# Attenuaverting_VCA.net
KiCad netlist of a schematic drawn in EAGLE
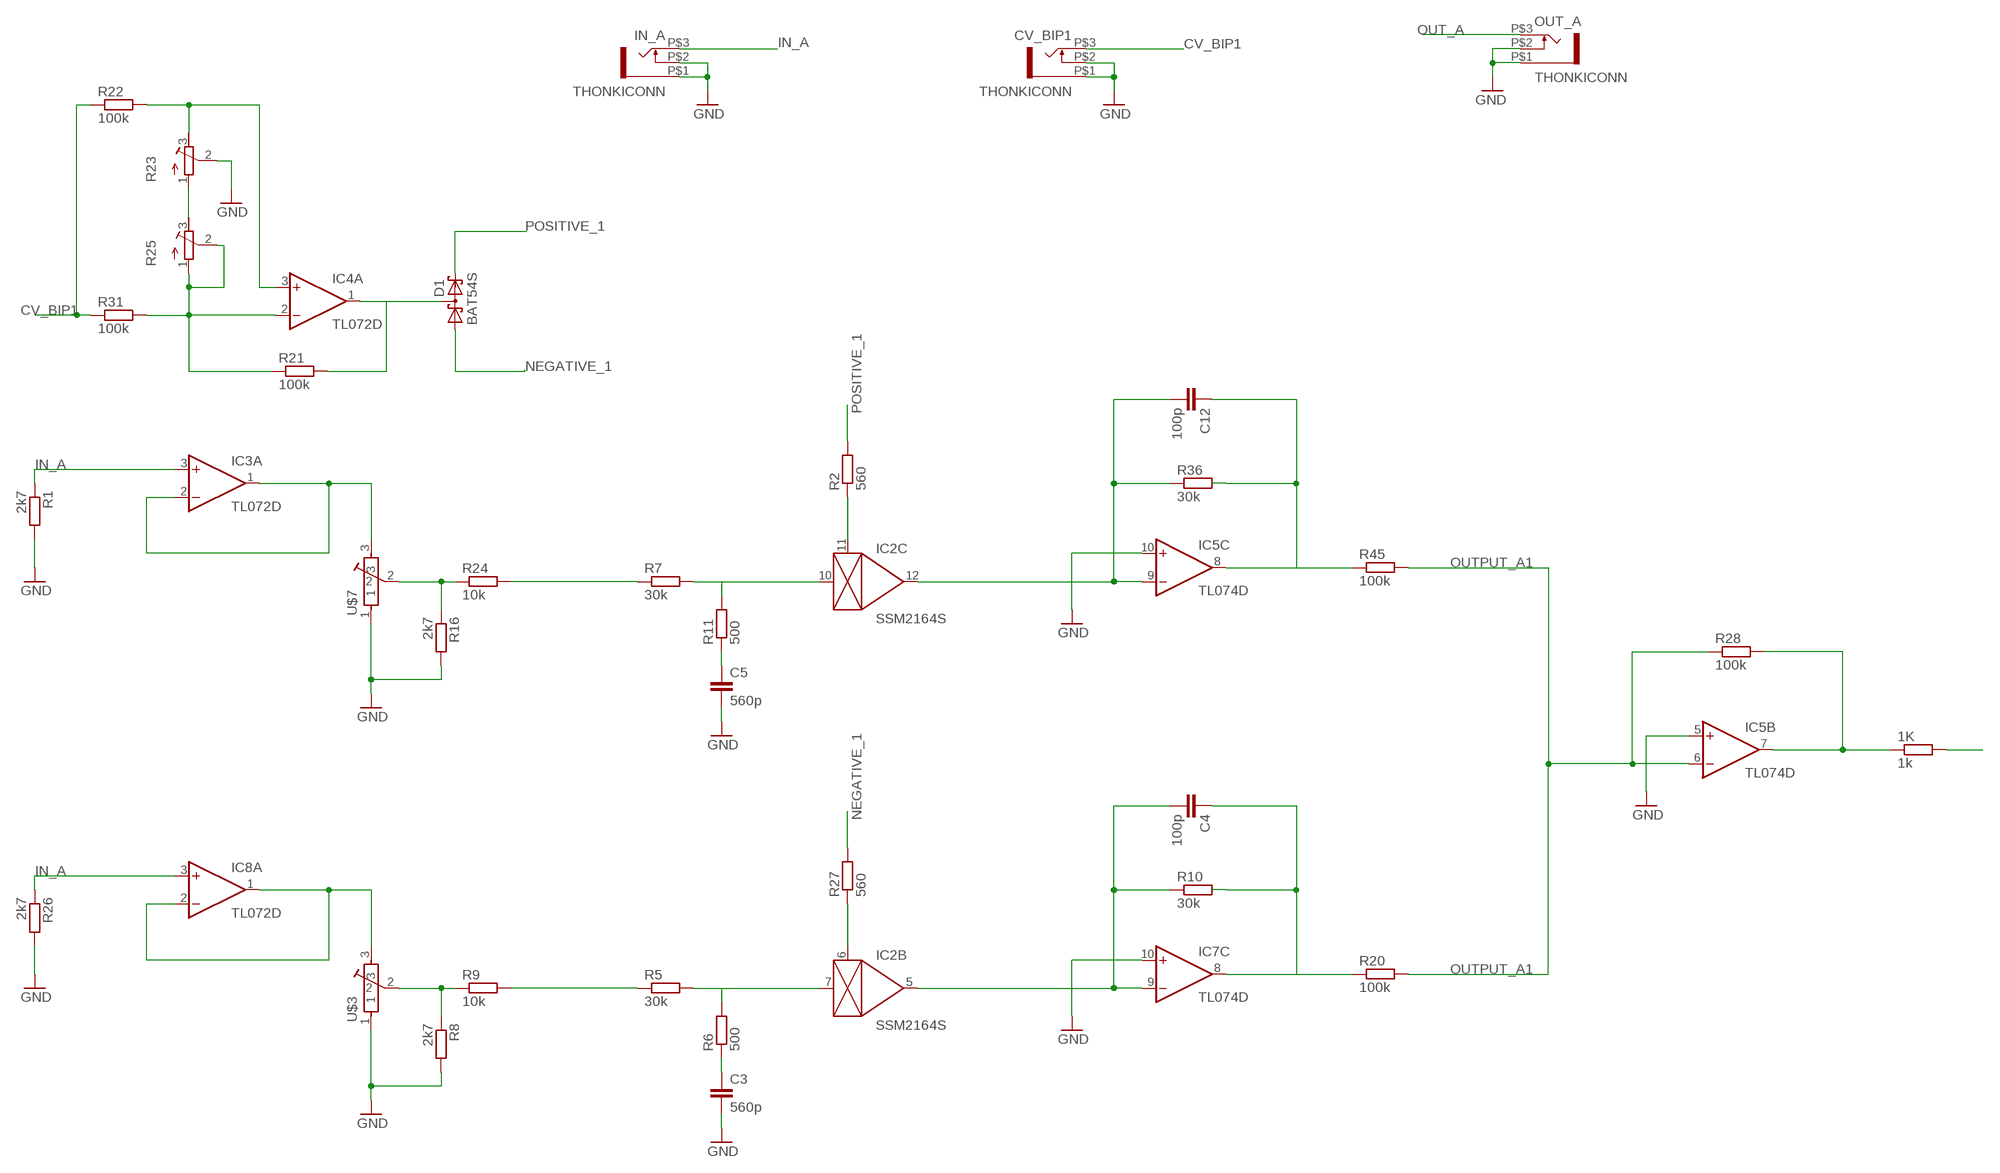
[diagram p0: schematic, sheet 1]

(export (version "E")
  (design (tool "Eeschema 10.0.6"))
  (components
    (comp (ref "1K")
      (value "1k")
      (footprint "eagle-import:0603")
      (libsource (lib "eagle-import") (part "R-EU_0603"))
    )
    (comp (ref "C3")
      (value "560p")
      (footprint "eagle-import:C0603K")
      (libsource (lib "eagle-import") (part "C-EUC0603K"))
    )
    (comp (ref "C4")
      (value "100p")
      (footprint "eagle-import:C0603K")
      (libsource (lib "eagle-import") (part "C-EUC0603K"))
    )
    (comp (ref "C5")
      (value "560p")
      (footprint "eagle-import:C0603K")
      (libsource (lib "eagle-import") (part "C-EUC0603K"))
    )
    (comp (ref "C12")
      (value "100p")
      (footprint "eagle-import:C0603K")
      (libsource (lib "eagle-import") (part "C-EUC0603K"))
    )
    (comp (ref "CV_BIP1")
      (value "THONKICONN")
      (footprint "eagle-import:THONKICONN")
      (libsource (lib "eagle-import") (part "THONKICONN"))
    )
    (comp (ref "D1")
      (value "BAT54S")
      (footprint "eagle-import:SOT23")
      (libsource (lib "eagle-import") (part "BAT54S"))
    )
    (comp (ref "IC2")
      (value "SSM2164S")
      (footprint "eagle-import:SOIC16N")
      (libsource (lib "eagle-import") (part "SSM2164S"))
    )
    (comp (ref "IC3")
      (value "TL072D")
      (footprint "eagle-import:SO08")
      (libsource (lib "eagle-import") (part "TL072D"))
    )
    (comp (ref "IC4")
      (value "TL072D")
      (footprint "eagle-import:SO08")
      (libsource (lib "eagle-import") (part "TL072D"))
    )
    (comp (ref "IC5")
      (value "TL074D")
      (footprint "eagle-import:SO14")
      (libsource (lib "eagle-import") (part "TL074D"))
    )
    (comp (ref "IC7")
      (value "TL074D")
      (footprint "eagle-import:SO14")
      (libsource (lib "eagle-import") (part "TL074D"))
    )
    (comp (ref "IC8")
      (value "TL072D")
      (footprint "eagle-import:SO08")
      (libsource (lib "eagle-import") (part "TL072D"))
    )
    (comp (ref "IN_A")
      (value "THONKICONN")
      (footprint "eagle-import:THONKICONN")
      (libsource (lib "eagle-import") (part "THONKICONN"))
    )
    (comp (ref "OUT_A")
      (value "THONKICONN")
      (footprint "eagle-import:THONKICONN")
      (libsource (lib "eagle-import") (part "THONKICONN"))
    )
    (comp (ref "R1")
      (value "2k7")
      (footprint "eagle-import:0603")
      (libsource (lib "eagle-import") (part "R-EU_0603"))
    )
    (comp (ref "R2")
      (value "560")
      (footprint "eagle-import:0603")
      (libsource (lib "eagle-import") (part "R-EU_0603"))
    )
    (comp (ref "R5")
      (value "30k")
      (footprint "eagle-import:0603")
      (libsource (lib "eagle-import") (part "R-EU_0603"))
    )
    (comp (ref "R6")
      (value "500")
      (footprint "eagle-import:0603")
      (libsource (lib "eagle-import") (part "R-EU_0603"))
    )
    (comp (ref "R7")
      (value "30k")
      (footprint "eagle-import:0603")
      (libsource (lib "eagle-import") (part "R-EU_0603"))
    )
    (comp (ref "R8")
      (value "2k7")
      (footprint "eagle-import:0603")
      (libsource (lib "eagle-import") (part "R-EU_0603"))
    )
    (comp (ref "R9")
      (value "10k")
      (footprint "eagle-import:0603")
      (libsource (lib "eagle-import") (part "R-EU_0603"))
    )
    (comp (ref "R10")
      (value "30k")
      (footprint "eagle-import:0603")
      (libsource (lib "eagle-import") (part "R-EU_0603"))
    )
    (comp (ref "R11")
      (value "500")
      (footprint "eagle-import:0603")
      (libsource (lib "eagle-import") (part "R-EU_0603"))
    )
    (comp (ref "R16")
      (value "2k7")
      (footprint "eagle-import:0603")
      (libsource (lib "eagle-import") (part "R-EU_0603"))
    )
    (comp (ref "R20")
      (value "100k")
      (footprint "eagle-import:0603")
      (libsource (lib "eagle-import") (part "R-EU_0603"))
    )
    (comp (ref "R21")
      (value "100k")
      (footprint "eagle-import:0603")
      (libsource (lib "eagle-import") (part "R-EU_0603"))
    )
    (comp (ref "R22")
      (value "100k")
      (footprint "eagle-import:0603")
      (libsource (lib "eagle-import") (part "R-EU_0603"))
    )
    (comp (ref "R23")
      (value "R-TRIMM64X")
      (footprint "eagle-import:RTRIM64X")
      (libsource (lib "eagle-import") (part "R-TRIMM64X"))
    )
    (comp (ref "R24")
      (value "10k")
      (footprint "eagle-import:0603")
      (libsource (lib "eagle-import") (part "R-EU_0603"))
    )
    (comp (ref "R25")
      (value "R-TRIMM64X")
      (footprint "eagle-import:RTRIM64X")
      (libsource (lib "eagle-import") (part "R-TRIMM64X"))
    )
    (comp (ref "R26")
      (value "2k7")
      (footprint "eagle-import:0603")
      (libsource (lib "eagle-import") (part "R-EU_0603"))
    )
    (comp (ref "R27")
      (value "560")
      (footprint "eagle-import:0603")
      (libsource (lib "eagle-import") (part "R-EU_0603"))
    )
    (comp (ref "R28")
      (value "100k")
      (footprint "eagle-import:0603")
      (libsource (lib "eagle-import") (part "R-EU_0603"))
    )
    (comp (ref "R31")
      (value "100k")
      (footprint "eagle-import:0603")
      (libsource (lib "eagle-import") (part "R-EU_0603"))
    )
    (comp (ref "R36")
      (value "30k")
      (footprint "eagle-import:0603")
      (libsource (lib "eagle-import") (part "R-EU_0603"))
    )
    (comp (ref "R45")
      (value "100k")
      (footprint "eagle-import:0603")
      (libsource (lib "eagle-import") (part "R-EU_0603"))
    )
    (comp (ref "U$3")
      (value "POT-ALPS-RK09L1140")
      (footprint "eagle-import:POT-ALPS-RK09L1140")
      (libsource (lib "eagle-import") (part "POT-ALPS-RK09L1140"))
    )
    (comp (ref "U$7")
      (value "POT-ALPS-RK09L1140")
      (footprint "eagle-import:POT-ALPS-RK09L1140")
      (libsource (lib "eagle-import") (part "POT-ALPS-RK09L1140"))
    )
  )
  (nets
    (net (code "1") (name "/CV_BIP1") (class "Default")
      (node (ref "CV_BIP1") (pin "P$3") (pinfunction "3_P$3") (pintype "passive"))
      (node (ref "R22") (pin "1") (pinfunction "1_1") (pintype "passive"))
      (node (ref "R31") (pin "1") (pinfunction "1_1") (pintype "passive"))
    )
    (net (code "2") (name "/IN_A") (class "Default")
      (node (ref "IC3") (pin "3") (pinfunction "+IN_3") (pintype "input"))
      (node (ref "IC8") (pin "3") (pinfunction "+IN_3") (pintype "input"))
      (node (ref "IN_A") (pin "P$3") (pinfunction "3_P$3") (pintype "passive"))
      (node (ref "R1") (pin "1") (pinfunction "1_1") (pintype "passive"))
      (node (ref "R26") (pin "1") (pinfunction "1_1") (pintype "passive"))
    )
    (net (code "3") (name "/NEGATIVE_1") (class "Default")
      (node (ref "D1") (pin "1") (pinfunction "A1_1") (pintype "passive"))
      (node (ref "R27") (pin "2") (pinfunction "2_2") (pintype "passive"))
    )
    (net (code "4") (name "/OUTPUT_A1") (class "Default")
      (node (ref "IC5") (pin "6") (pinfunction "-IN_6") (pintype "input"))
      (node (ref "R20") (pin "2") (pinfunction "2_2") (pintype "passive"))
      (node (ref "R28") (pin "1") (pinfunction "1_1") (pintype "passive"))
      (node (ref "R45") (pin "2") (pinfunction "2_2") (pintype "passive"))
    )
    (net (code "5") (name "/OUT_A") (class "Default")
      (node (ref "1K") (pin "2") (pinfunction "2_2") (pintype "passive"))
      (node (ref "OUT_A") (pin "P$3") (pinfunction "3_P$3") (pintype "passive"))
    )
    (net (code "6") (name "/POSITIVE_1") (class "Default")
      (node (ref "D1") (pin "2") (pinfunction "C2_2") (pintype "passive"))
      (node (ref "R2") (pin "2") (pinfunction "2_2") (pintype "passive"))
    )
    (net (code "7") (name "GND") (class "Default")
      (node (ref "C3") (pin "2") (pinfunction "2_2") (pintype "passive"))
      (node (ref "C5") (pin "2") (pinfunction "2_2") (pintype "passive"))
      (node (ref "CV_BIP1") (pin "P$1") (pinfunction "5_P$1") (pintype "passive"))
      (node (ref "CV_BIP1") (pin "P$2") (pinfunction "4_P$2") (pintype "passive"))
      (node (ref "IC5") (pin "10") (pinfunction "+IN_10") (pintype "input"))
      (node (ref "IC5") (pin "5") (pinfunction "+IN_5") (pintype "input"))
      (node (ref "IC7") (pin "10") (pinfunction "+IN_10") (pintype "input"))
      (node (ref "IN_A") (pin "P$1") (pinfunction "5_P$1") (pintype "passive"))
      (node (ref "IN_A") (pin "P$2") (pinfunction "4_P$2") (pintype "passive"))
      (node (ref "OUT_A") (pin "P$1") (pinfunction "5_P$1") (pintype "passive"))
      (node (ref "OUT_A") (pin "P$2") (pinfunction "4_P$2") (pintype "passive"))
      (node (ref "R1") (pin "2") (pinfunction "2_2") (pintype "passive"))
      (node (ref "R16") (pin "2") (pinfunction "2_2") (pintype "passive"))
      (node (ref "R23") (pin "2") (pinfunction "S_2") (pintype "passive"))
      (node (ref "R26") (pin "2") (pinfunction "2_2") (pintype "passive"))
      (node (ref "R8") (pin "2") (pinfunction "2_2") (pintype "passive"))
      (node (ref "U$3") (pin "1") (pinfunction "1_1") (pintype "bidirectional"))
      (node (ref "U$7") (pin "1") (pinfunction "1_1") (pintype "bidirectional"))
    )
    (net (code "8") (name "Net-(C3-Pad1)") (class "Default")
      (node (ref "C3") (pin "1") (pinfunction "1_1") (pintype "passive"))
      (node (ref "R6") (pin "1") (pinfunction "1_1") (pintype "passive"))
    )
    (net (code "9") (name "Net-(C5-Pad1)") (class "Default")
      (node (ref "C5") (pin "1") (pinfunction "1_1") (pintype "passive"))
      (node (ref "R11") (pin "1") (pinfunction "1_1") (pintype "passive"))
    )
    (net (code "10") (name "Net-(D1-C1A2)") (class "Default")
      (node (ref "D1") (pin "3") (pinfunction "C1A2_3") (pintype "passive"))
      (node (ref "IC4") (pin "1") (pinfunction "OUT_1") (pintype "output"))
      (node (ref "R21") (pin "2") (pinfunction "2_2") (pintype "passive"))
    )
    (net (code "11") (name "Net-(IC2B-CTRL)") (class "Default")
      (node (ref "IC2") (pin "6") (pinfunction "CTRL_6") (pintype "input"))
      (node (ref "R27") (pin "1") (pinfunction "1_1") (pintype "passive"))
    )
    (net (code "12") (name "Net-(IC2B-IN)") (class "Default")
      (node (ref "IC2") (pin "7") (pinfunction "IN_7") (pintype "input"))
      (node (ref "R5") (pin "2") (pinfunction "2_2") (pintype "passive"))
      (node (ref "R6") (pin "2") (pinfunction "2_2") (pintype "passive"))
    )
    (net (code "13") (name "Net-(IC2B-OUT)") (class "Default")
      (node (ref "C4") (pin "2") (pinfunction "2_2") (pintype "passive"))
      (node (ref "IC2") (pin "5") (pinfunction "OUT_5") (pintype "output"))
      (node (ref "IC7") (pin "9") (pinfunction "-IN_9") (pintype "input"))
      (node (ref "R10") (pin "1") (pinfunction "1_1") (pintype "passive"))
    )
    (net (code "14") (name "Net-(IC2C-CTRL)") (class "Default")
      (node (ref "IC2") (pin "11") (pinfunction "CTRL_11") (pintype "input"))
      (node (ref "R2") (pin "1") (pinfunction "1_1") (pintype "passive"))
    )
    (net (code "15") (name "Net-(IC2C-IN)") (class "Default")
      (node (ref "IC2") (pin "10") (pinfunction "IN_10") (pintype "input"))
      (node (ref "R11") (pin "2") (pinfunction "2_2") (pintype "passive"))
      (node (ref "R7") (pin "2") (pinfunction "2_2") (pintype "passive"))
    )
    (net (code "16") (name "Net-(IC2C-OUT)") (class "Default")
      (node (ref "C12") (pin "2") (pinfunction "2_2") (pintype "passive"))
      (node (ref "IC2") (pin "12") (pinfunction "OUT_12") (pintype "output"))
      (node (ref "IC5") (pin "9") (pinfunction "-IN_9") (pintype "input"))
      (node (ref "R36") (pin "1") (pinfunction "1_1") (pintype "passive"))
    )
    (net (code "17") (name "Net-(IC3A--IN)") (class "Default")
      (node (ref "IC3") (pin "1") (pinfunction "OUT_1") (pintype "output"))
      (node (ref "IC3") (pin "2") (pinfunction "-IN_2") (pintype "input"))
      (node (ref "U$7") (pin "3") (pinfunction "3_3") (pintype "bidirectional"))
    )
    (net (code "18") (name "Net-(IC4A-+IN)") (class "Default")
      (node (ref "IC4") (pin "3") (pinfunction "+IN_3") (pintype "input"))
      (node (ref "R22") (pin "2") (pinfunction "2_2") (pintype "passive"))
      (node (ref "R23") (pin "3") (pinfunction "E_3") (pintype "passive"))
    )
    (net (code "19") (name "Net-(IC4A--IN)") (class "Default")
      (node (ref "IC4") (pin "2") (pinfunction "-IN_2") (pintype "input"))
      (node (ref "R21") (pin "1") (pinfunction "1_1") (pintype "passive"))
      (node (ref "R25") (pin "1") (pinfunction "A_1") (pintype "passive"))
      (node (ref "R25") (pin "2") (pinfunction "S_2") (pintype "passive"))
      (node (ref "R31") (pin "2") (pinfunction "2_2") (pintype "passive"))
    )
    (net (code "20") (name "Net-(IC5B-OUT)") (class "Default")
      (node (ref "1K") (pin "1") (pinfunction "1_1") (pintype "passive"))
      (node (ref "IC5") (pin "7") (pinfunction "OUT_7") (pintype "output"))
      (node (ref "R28") (pin "2") (pinfunction "2_2") (pintype "passive"))
    )
    (net (code "21") (name "Net-(IC5C-OUT)") (class "Default")
      (node (ref "C12") (pin "1") (pinfunction "1_1") (pintype "passive"))
      (node (ref "IC5") (pin "8") (pinfunction "OUT_8") (pintype "output"))
      (node (ref "R36") (pin "2") (pinfunction "2_2") (pintype "passive"))
      (node (ref "R45") (pin "1") (pinfunction "1_1") (pintype "passive"))
    )
    (net (code "22") (name "Net-(IC7C-OUT)") (class "Default")
      (node (ref "C4") (pin "1") (pinfunction "1_1") (pintype "passive"))
      (node (ref "IC7") (pin "8") (pinfunction "OUT_8") (pintype "output"))
      (node (ref "R10") (pin "2") (pinfunction "2_2") (pintype "passive"))
      (node (ref "R20") (pin "1") (pinfunction "1_1") (pintype "passive"))
    )
    (net (code "23") (name "Net-(IC8A--IN)") (class "Default")
      (node (ref "IC8") (pin "1") (pinfunction "OUT_1") (pintype "output"))
      (node (ref "IC8") (pin "2") (pinfunction "-IN_2") (pintype "input"))
      (node (ref "U$3") (pin "3") (pinfunction "3_3") (pintype "bidirectional"))
    )
    (net (code "24") (name "Net-(R5-Pad1)") (class "Default")
      (node (ref "R5") (pin "1") (pinfunction "1_1") (pintype "passive"))
      (node (ref "R9") (pin "2") (pinfunction "2_2") (pintype "passive"))
    )
    (net (code "25") (name "Net-(R8-Pad1)") (class "Default")
      (node (ref "R8") (pin "1") (pinfunction "1_1") (pintype "passive"))
      (node (ref "R9") (pin "1") (pinfunction "1_1") (pintype "passive"))
      (node (ref "U$3") (pin "2") (pinfunction "2_2") (pintype "bidirectional"))
    )
    (net (code "26") (name "Net-(R16-Pad1)") (class "Default")
      (node (ref "R16") (pin "1") (pinfunction "1_1") (pintype "passive"))
      (node (ref "R24") (pin "1") (pinfunction "1_1") (pintype "passive"))
      (node (ref "U$7") (pin "2") (pinfunction "2_2") (pintype "bidirectional"))
    )
    (net (code "27") (name "Net-(R23-A)") (class "Default")
      (node (ref "R23") (pin "1") (pinfunction "A_1") (pintype "passive"))
      (node (ref "R25") (pin "3") (pinfunction "E_3") (pintype "passive"))
    )
    (net (code "28") (name "Net-(R24-Pad2)") (class "Default")
      (node (ref "R24") (pin "2") (pinfunction "2_2") (pintype "passive"))
      (node (ref "R7") (pin "1") (pinfunction "1_1") (pintype "passive"))
    )
  )
)
